# ATtiny10_Writer.net
KiCad netlist of a schematic drawn in EAGLE
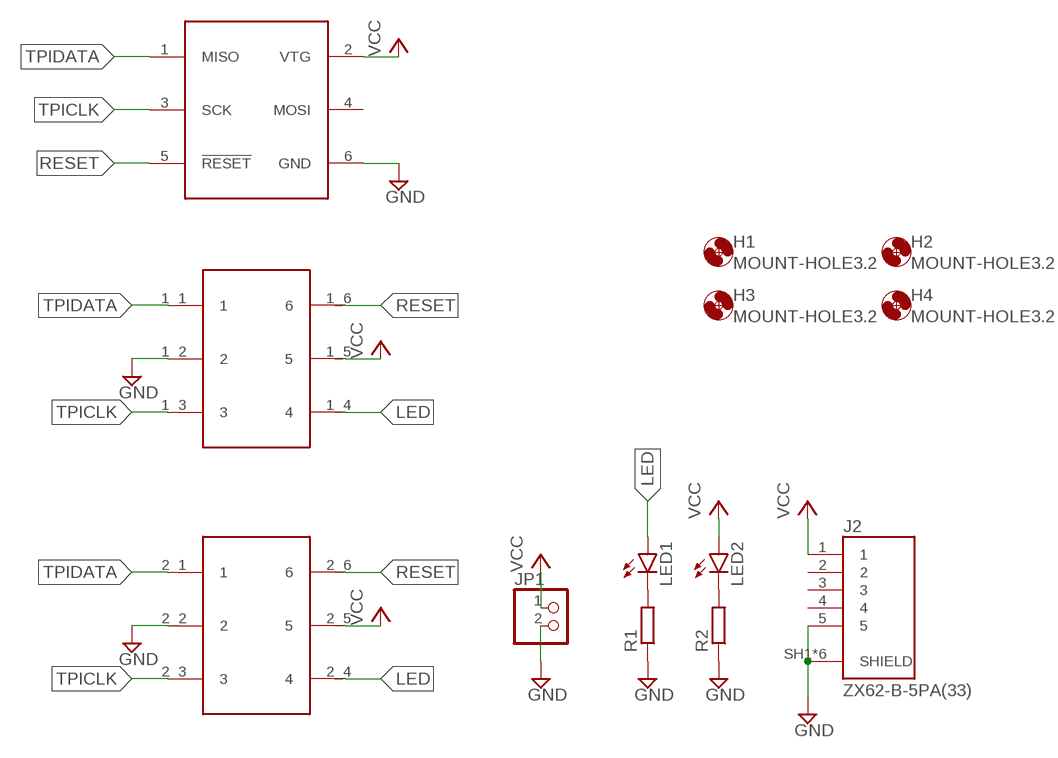
[diagram p0: schematic, sheet 1]

(export (version "E")
  (design (tool "Eeschema 10.0.6"))
  (components
    (comp (ref "CON1")
      (value "AVR_ISP")
      (footprint "eagle-import:AVR_ISP")
      (libsource (lib "eagle-import") (part "AVR_ISP"))
    )
    (comp (ref "H1")
      (value "MOUNT-HOLE3.2")
      (footprint "eagle-import:3,2")
      (libsource (lib "eagle-import") (part "MOUNT-HOLE3.2"))
    )
    (comp (ref "H2")
      (value "MOUNT-HOLE3.2")
      (footprint "eagle-import:3,2")
      (libsource (lib "eagle-import") (part "MOUNT-HOLE3.2"))
    )
    (comp (ref "H3")
      (value "MOUNT-HOLE3.2")
      (footprint "eagle-import:3,2")
      (libsource (lib "eagle-import") (part "MOUNT-HOLE3.2"))
    )
    (comp (ref "H4")
      (value "MOUNT-HOLE3.2")
      (footprint "eagle-import:3,2")
      (libsource (lib "eagle-import") (part "MOUNT-HOLE3.2"))
    )
    (comp (ref "J1")
      (value "SOT23-6_2_SOCKET")
      (footprint "eagle-import:IC_SOCKET_051-2317-060")
      (libsource (lib "eagle-import") (part "SOT23-6_2_SOCKET"))
    )
    (comp (ref "J2")
      (value "ZX62-B-5PA(33)")
      (footprint "eagle-import:HRS_ZX62-B-5PA(33)")
      (fields (field (name "MF") "Hirose") (field (name "MP") "ZX62-B-5PA_33_"))
      (libsource (lib "eagle-import") (part "ZX62-B-5PA(33)"))
    )
    (comp (ref "JP1")
      (value "PINHD-1X2")
      (footprint "eagle-import:1X02")
      (libsource (lib "eagle-import") (part "PINHD-1X2"))
    )
    (comp (ref "LED1")
      (value "LEDCHIP-LED0603")
      (footprint "eagle-import:CHIP-LED0603")
      (libsource (lib "eagle-import") (part "LEDCHIP-LED0603"))
    )
    (comp (ref "LED2")
      (value "LEDCHIP-LED0603")
      (footprint "eagle-import:CHIP-LED0603")
      (libsource (lib "eagle-import") (part "LEDCHIP-LED0603"))
    )
    (comp (ref "R1")
      (value "R-EU_R0603")
      (footprint "eagle-import:R0603")
      (libsource (lib "eagle-import") (part "R-EU_R0603"))
    )
    (comp (ref "R2")
      (value "R-EU_R0603")
      (footprint "eagle-import:R0603")
      (libsource (lib "eagle-import") (part "R-EU_R0603"))
    )
  )
  (nets
    (net (code "1") (name "GND") (class "Default")
      (node (ref "CON1") (pin "6") (pinfunction "GND_6") (pintype "bidirectional"))
      (node (ref "J1") (pin "1_2") (pinfunction "2_1_2") (pintype "bidirectional"))
      (node (ref "J1") (pin "2_2") (pinfunction "2_2_2") (pintype "bidirectional"))
      (node (ref "J2") (pin "5") (pinfunction "5_5") (pintype "passive"))
      (node (ref "J2") (pin "SH1") (pinfunction "SHIELD_SH1") (pintype "passive"))
      (node (ref "J2") (pin "SH2") (pinfunction "SHIELD_SH2") (pintype "passive"))
      (node (ref "J2") (pin "SH3") (pinfunction "SHIELD_SH3") (pintype "passive"))
      (node (ref "J2") (pin "SH4") (pinfunction "SHIELD_SH4") (pintype "passive"))
      (node (ref "J2") (pin "SH5") (pinfunction "SHIELD_SH5") (pintype "passive"))
      (node (ref "J2") (pin "SH6") (pinfunction "SHIELD_SH6") (pintype "passive"))
      (node (ref "JP1") (pin "2") (pinfunction "2_2") (pintype "passive"))
      (node (ref "R1") (pin "1") (pinfunction "1_1") (pintype "passive"))
      (node (ref "R2") (pin "1") (pinfunction "1_1") (pintype "passive"))
    )
    (net (code "2") (name "LED") (class "Default")
      (node (ref "J1") (pin "1_4") (pinfunction "4_1_4") (pintype "bidirectional"))
      (node (ref "J1") (pin "2_4") (pinfunction "4_2_4") (pintype "bidirectional"))
      (node (ref "LED1") (pin "A") (pinfunction "A_A") (pintype "passive"))
    )
    (net (code "3") (name "Net-(LED1-PadC)") (class "Default")
      (node (ref "LED1") (pin "C") (pinfunction "C_C") (pintype "passive"))
      (node (ref "R1") (pin "2") (pinfunction "2_2") (pintype "passive"))
    )
    (net (code "4") (name "Net-(LED2-PadC)") (class "Default")
      (node (ref "LED2") (pin "C") (pinfunction "C_C") (pintype "passive"))
      (node (ref "R2") (pin "2") (pinfunction "2_2") (pintype "passive"))
    )
    (net (code "5") (name "RESET") (class "Default")
      (node (ref "CON1") (pin "5") (pinfunction "~{RESET}_5") (pintype "bidirectional"))
      (node (ref "J1") (pin "1_6") (pinfunction "6_1_6") (pintype "bidirectional"))
      (node (ref "J1") (pin "2_6") (pinfunction "6_2_6") (pintype "bidirectional"))
    )
    (net (code "6") (name "TPICLK") (class "Default")
      (node (ref "CON1") (pin "3") (pinfunction "SCK_3") (pintype "bidirectional"))
      (node (ref "J1") (pin "1_3") (pinfunction "3_1_3") (pintype "bidirectional"))
      (node (ref "J1") (pin "2_3") (pinfunction "3_2_3") (pintype "bidirectional"))
    )
    (net (code "7") (name "TPIDATA") (class "Default")
      (node (ref "CON1") (pin "1") (pinfunction "MISO_1") (pintype "bidirectional"))
      (node (ref "J1") (pin "1_1") (pinfunction "1_1_1") (pintype "bidirectional"))
      (node (ref "J1") (pin "2_1") (pinfunction "1_2_1") (pintype "bidirectional"))
    )
    (net (code "8") (name "VCC") (class "Default")
      (node (ref "CON1") (pin "2") (pinfunction "VTG_2") (pintype "bidirectional"))
      (node (ref "J1") (pin "1_5") (pinfunction "5_1_5") (pintype "bidirectional"))
      (node (ref "J1") (pin "2_5") (pinfunction "5_2_5") (pintype "bidirectional"))
      (node (ref "J2") (pin "1") (pinfunction "1_1") (pintype "passive"))
      (node (ref "JP1") (pin "1") (pinfunction "1_1") (pintype "passive"))
      (node (ref "LED2") (pin "A") (pinfunction "A_A") (pintype "passive"))
    )
    (net (code "9") (name "unconnected-(CON1-MOSI-Pad4)") (class "Default")
      (node (ref "CON1") (pin "4") (pinfunction "MOSI_4") (pintype "bidirectional"))
    )
    (net (code "10") (name "unconnected-(J2-Pad2)") (class "Default")
      (node (ref "J2") (pin "2") (pinfunction "2_2") (pintype "passive"))
    )
    (net (code "11") (name "unconnected-(J2-Pad3)") (class "Default")
      (node (ref "J2") (pin "3") (pinfunction "3_3") (pintype "passive"))
    )
    (net (code "12") (name "unconnected-(J2-Pad4)") (class "Default")
      (node (ref "J2") (pin "4") (pinfunction "4_4") (pintype "passive"))
    )
  )
)
